# DCP23.net
KiCad netlist of a schematic drawn in EAGLE
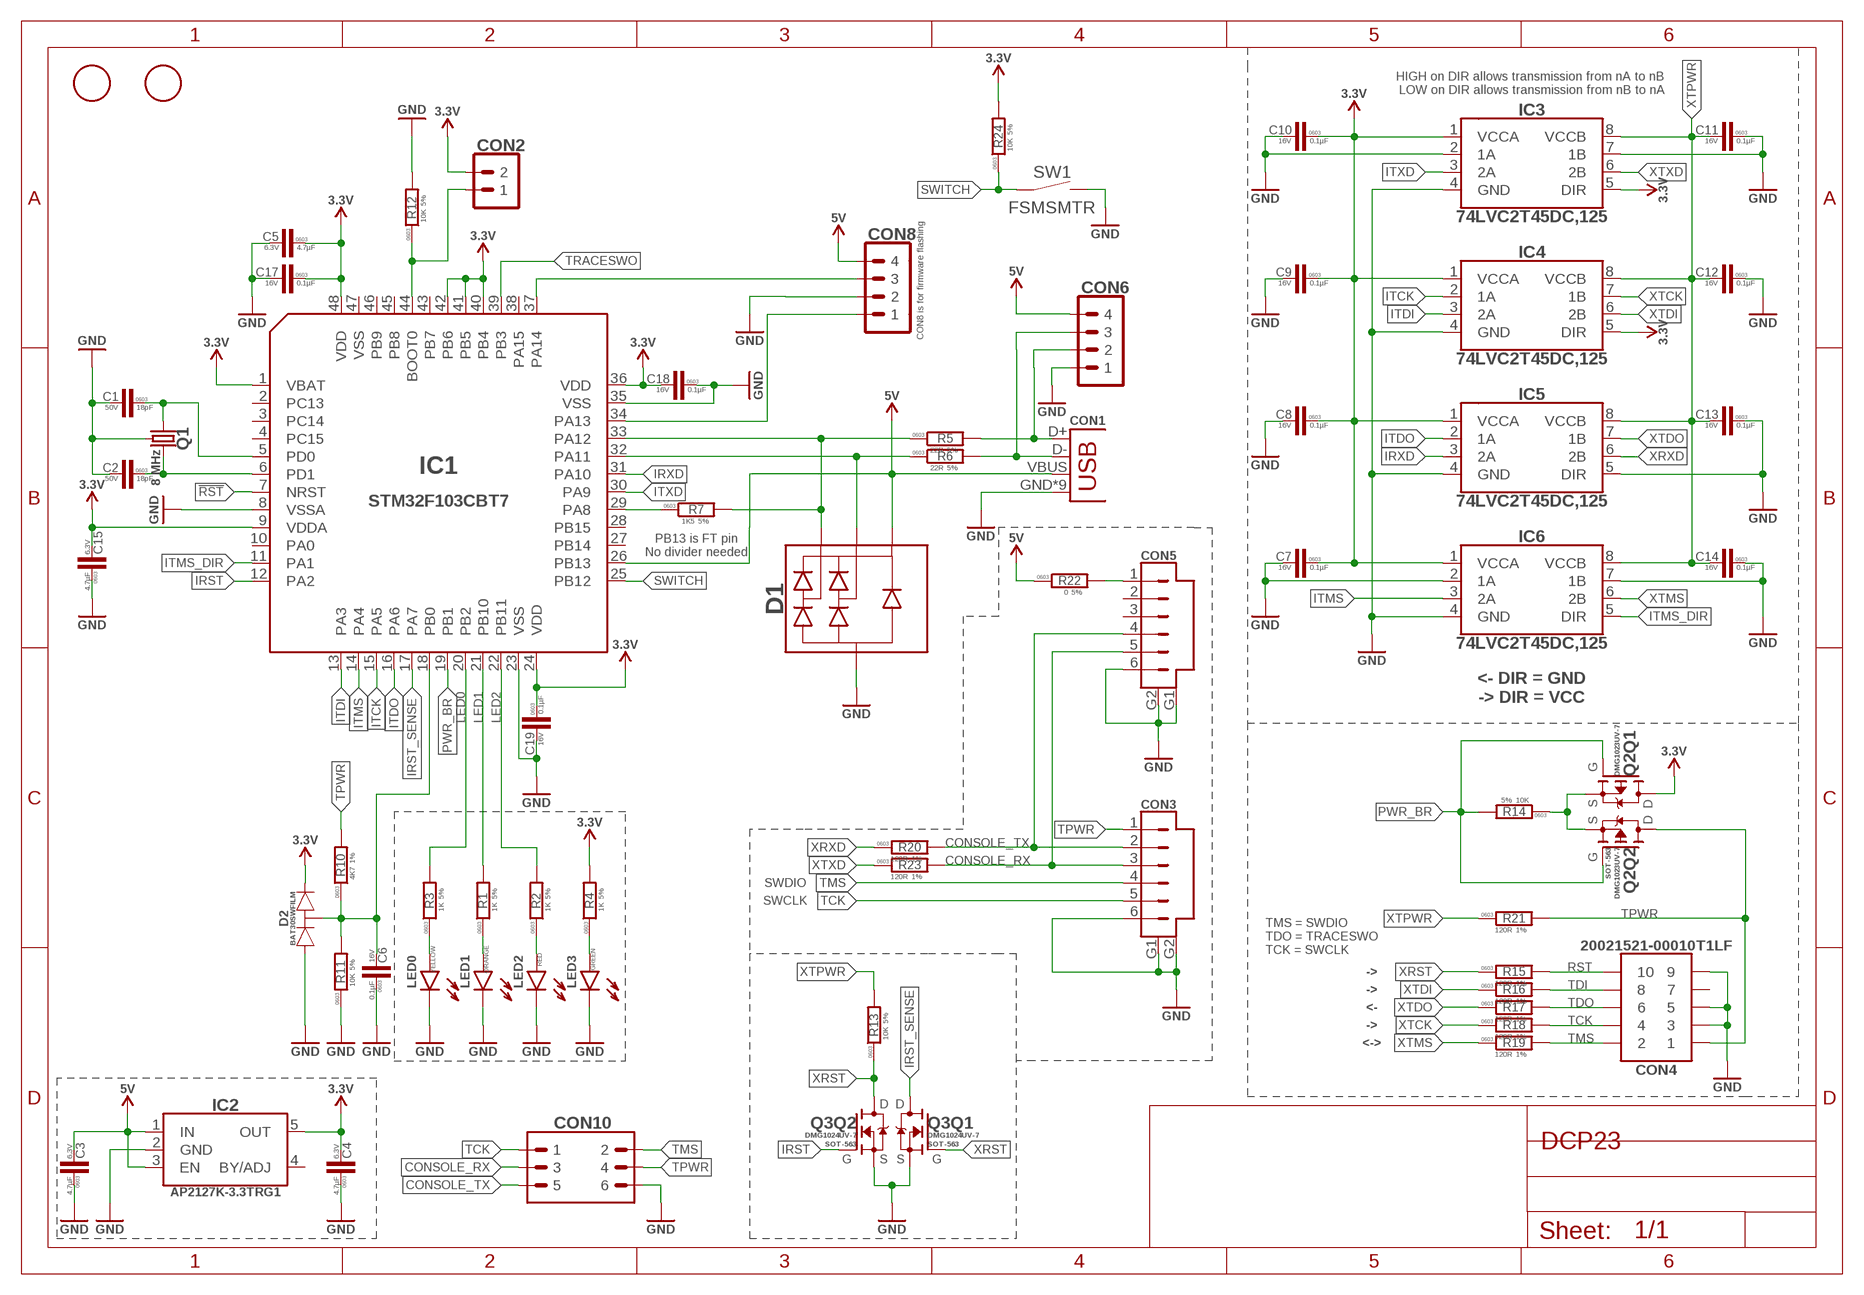
[diagram p0: schematic, sheet 1]

(export (version "E")
  (design (tool "Eeschema 10.0.6"))
  (components
    (comp (ref "C1")
      (value "18pF")
      (footprint "eagle-import:C0603")
      (fields
        (field (name "MANF") "TDK Corporation")
        (field (name "PACKAGE") "0603")
        (field (name "TOLERANCE") "+-5%")
        (field (name "VOLTAGE") "50V")
      )
      (libsource (lib "eagle-import") (part "18PF-0603-50V_5%_NP0"))
    )
    (comp (ref "C2")
      (value "18pF")
      (footprint "eagle-import:C0603")
      (fields
        (field (name "MANF") "TDK Corporation")
        (field (name "PACKAGE") "0603")
        (field (name "TOLERANCE") "+-5%")
        (field (name "VOLTAGE") "50V")
      )
      (libsource (lib "eagle-import") (part "18PF-0603-50V_5%_NP0"))
    )
    (comp (ref "C3")
      (value "4.7µF")
      (footprint "eagle-import:C0603")
      (fields
        (field (name "MANF") "Murata Electronics North America")
        (field (name "PACKAGE") "0603")
        (field (name "TOLERANCE") "+-10%")
        (field (name "VOLTAGE") "6.3V")
      )
      (libsource (lib "eagle-import") (part "4.7µF-0603-6.3V_10%_X5R"))
    )
    (comp (ref "C4")
      (value "4.7µF")
      (footprint "eagle-import:C0603")
      (fields
        (field (name "MANF") "Murata Electronics North America")
        (field (name "PACKAGE") "0603")
        (field (name "TOLERANCE") "+-10%")
        (field (name "VOLTAGE") "6.3V")
      )
      (libsource (lib "eagle-import") (part "4.7µF-0603-6.3V_10%_X5R"))
    )
    (comp (ref "C5")
      (value "4.7µF")
      (footprint "eagle-import:C0603")
      (fields
        (field (name "MANF") "Murata Electronics North America")
        (field (name "PACKAGE") "0603")
        (field (name "TOLERANCE") "+-10%")
        (field (name "VOLTAGE") "6.3V")
      )
      (libsource (lib "eagle-import") (part "4.7µF-0603-6.3V_10%_X5R"))
    )
    (comp (ref "C6")
      (value "0.1µF")
      (footprint "eagle-import:C0603")
      (fields
        (field (name "MANF") "Murata Electronics North America")
        (field (name "PACKAGE") "0603")
        (field (name "TOLERANCE") "+-10%")
        (field (name "VOLTAGE") "16V")
      )
      (libsource (lib "eagle-import") (part "0.1µF-0603-16V_10%_X7R"))
    )
    (comp (ref "C7")
      (value "0.1µF")
      (footprint "eagle-import:C0603")
      (fields
        (field (name "MANF") "Murata Electronics North America")
        (field (name "PACKAGE") "0603")
        (field (name "TOLERANCE") "+-10%")
        (field (name "VOLTAGE") "16V")
      )
      (libsource (lib "eagle-import") (part "0.1µF-0603-16V_10%_X7R"))
    )
    (comp (ref "C8")
      (value "0.1µF")
      (footprint "eagle-import:C0603")
      (fields
        (field (name "MANF") "Murata Electronics North America")
        (field (name "PACKAGE") "0603")
        (field (name "TOLERANCE") "+-10%")
        (field (name "VOLTAGE") "16V")
      )
      (libsource (lib "eagle-import") (part "0.1µF-0603-16V_10%_X7R"))
    )
    (comp (ref "C9")
      (value "0.1µF")
      (footprint "eagle-import:C0603")
      (fields
        (field (name "MANF") "Murata Electronics North America")
        (field (name "PACKAGE") "0603")
        (field (name "TOLERANCE") "+-10%")
        (field (name "VOLTAGE") "16V")
      )
      (libsource (lib "eagle-import") (part "0.1µF-0603-16V_10%_X7R"))
    )
    (comp (ref "C10")
      (value "0.1µF")
      (footprint "eagle-import:C0603")
      (fields
        (field (name "MANF") "Murata Electronics North America")
        (field (name "PACKAGE") "0603")
        (field (name "TOLERANCE") "+-10%")
        (field (name "VOLTAGE") "16V")
      )
      (libsource (lib "eagle-import") (part "0.1µF-0603-16V_10%_X7R"))
    )
    (comp (ref "C11")
      (value "0.1µF")
      (footprint "eagle-import:C0603")
      (fields
        (field (name "MANF") "Murata Electronics North America")
        (field (name "PACKAGE") "0603")
        (field (name "TOLERANCE") "+-10%")
        (field (name "VOLTAGE") "16V")
      )
      (libsource (lib "eagle-import") (part "0.1µF-0603-16V_10%_X7R"))
    )
    (comp (ref "C12")
      (value "0.1µF")
      (footprint "eagle-import:C0603")
      (fields
        (field (name "MANF") "Murata Electronics North America")
        (field (name "PACKAGE") "0603")
        (field (name "TOLERANCE") "+-10%")
        (field (name "VOLTAGE") "16V")
      )
      (libsource (lib "eagle-import") (part "0.1µF-0603-16V_10%_X7R"))
    )
    (comp (ref "C13")
      (value "0.1µF")
      (footprint "eagle-import:C0603")
      (fields
        (field (name "MANF") "Murata Electronics North America")
        (field (name "PACKAGE") "0603")
        (field (name "TOLERANCE") "+-10%")
        (field (name "VOLTAGE") "16V")
      )
      (libsource (lib "eagle-import") (part "0.1µF-0603-16V_10%_X7R"))
    )
    (comp (ref "C14")
      (value "0.1µF")
      (footprint "eagle-import:C0603")
      (fields
        (field (name "MANF") "Murata Electronics North America")
        (field (name "PACKAGE") "0603")
        (field (name "TOLERANCE") "+-10%")
        (field (name "VOLTAGE") "16V")
      )
      (libsource (lib "eagle-import") (part "0.1µF-0603-16V_10%_X7R"))
    )
    (comp (ref "C15")
      (value "4.7µF")
      (footprint "eagle-import:C0603")
      (fields
        (field (name "MANF") "Murata Electronics North America")
        (field (name "PACKAGE") "0603")
        (field (name "TOLERANCE") "+-10%")
        (field (name "VOLTAGE") "6.3V")
      )
      (libsource (lib "eagle-import") (part "4.7µF-0603-6.3V_10%_X5R"))
    )
    (comp (ref "C17")
      (value "0.1µF")
      (footprint "eagle-import:C0603")
      (fields
        (field (name "MANF") "Murata Electronics North America")
        (field (name "PACKAGE") "0603")
        (field (name "TOLERANCE") "+-10%")
        (field (name "VOLTAGE") "16V")
      )
      (libsource (lib "eagle-import") (part "0.1µF-0603-16V_10%_X7R"))
    )
    (comp (ref "C18")
      (value "0.1µF")
      (footprint "eagle-import:C0603")
      (fields
        (field (name "MANF") "Murata Electronics North America")
        (field (name "PACKAGE") "0603")
        (field (name "TOLERANCE") "+-10%")
        (field (name "VOLTAGE") "16V")
      )
      (libsource (lib "eagle-import") (part "0.1µF-0603-16V_10%_X7R"))
    )
    (comp (ref "C19")
      (value "0.1µF")
      (footprint "eagle-import:C0603")
      (fields
        (field (name "MANF") "Murata Electronics North America")
        (field (name "PACKAGE") "0603")
        (field (name "TOLERANCE") "+-10%")
        (field (name "VOLTAGE") "16V")
      )
      (libsource (lib "eagle-import") (part "0.1µF-0603-16V_10%_X7R"))
    )
    (comp (ref "CON1")
      (value "USB-1")
      (footprint "eagle-import:MICRO_USB_WITH_PEGS")
      (fields (field (name "MANF") "FCI"))
      (libsource (lib "eagle-import") (part "USB-1"))
    )
    (comp (ref "CON2")
      (value "PINHEAD_1X02-2")
      (footprint "eagle-import:1X02-PTH-2")
      (libsource (lib "eagle-import") (part "PINHEAD_1X02-2"))
    )
    (comp (ref "CON3")
      (value "CON-6P-SM06B")
      (footprint "eagle-import:SM06B")
      (fields (field (name "MANF") "JST Sales America Inc"))
      (libsource (lib "eagle-import") (part "CON-6P-SM06B"))
    )
    (comp (ref "CON4")
      (value "CON-2X5P")
      (footprint "eagle-import:200215-00010T1LF")
      (fields (field (name "MANF#") "20021521-00010T1LF") (field (name "MANF") "Amphenol ICC (FCI)"))
      (libsource (lib "eagle-import") (part "CON-2X5P"))
    )
    (comp (ref "CON5")
      (value "CON-6P-DF13")
      (footprint "eagle-import:DF13C-6P-1.25V")
      (fields (field (name "MANF") "Hirose Electric Co Ltd"))
      (libsource (lib "eagle-import") (part "CON-6P-DF13"))
    )
    (comp (ref "CON6")
      (value "PINHEAD_1X04-2.54")
      (footprint "eagle-import:1X04-PTH-2.54")
      (libsource (lib "eagle-import") (part "PINHEAD_1X04-2.54"))
    )
    (comp (ref "CON8")
      (value "PINHEAD_1X04-2.54")
      (footprint "eagle-import:1X04-PTH-2.54")
      (libsource (lib "eagle-import") (part "PINHEAD_1X04-2.54"))
    )
    (comp (ref "CON10")
      (value "PINHEAD_2X03-PTH-2.54")
      (footprint "eagle-import:2X03-PTH-2.54")
      (libsource (lib "eagle-import") (part "PINHEAD_2X03-PTH-2.54"))
    )
    (comp (ref "D1")
      (value "PRTR5V0U2X")
      (footprint "eagle-import:SOT143B")
      (fields (field (name "MANF") "NXP USA Inc"))
      (libsource (lib "eagle-import") (part "PRTR5V0U2X"))
    )
    (comp (ref "D2")
      (value "BAT30SWFILM")
      (footprint "eagle-import:SC70")
      (fields (field (name "MANF#") "BAT30SWFILM") (field (name "MANF") "STMicroelectronics"))
      (libsource (lib "eagle-import") (part "BAT30SWFILM"))
    )
    (comp (ref "IC1")
      (value "STM32F103CBT7")
      (footprint "eagle-import:LQFP48")
      (fields (field (name "MANF#") "STM32F103CBT7") (field (name "MANF") "STMicroelectronics"))
      (libsource (lib "eagle-import") (part "STM32F103CBT7"))
    )
    (comp (ref "IC2")
      (value "AP2127-3.3")
      (footprint "eagle-import:SOT23-5")
      (fields (field (name "MANF") "Diodes Incorporated") (field (name "MANF#") "AP2127K-3.3TRG1"))
      (libsource (lib "eagle-import") (part "AP2127-3.3"))
    )
    (comp (ref "IC3")
      (value "74LVC2T45")
      (footprint "eagle-import:VSSOP8")
      (fields (field (name "MANF#") "74LVC2T45DC,125") (field (name "MANF") "Nexperia USA Inc"))
      (libsource (lib "eagle-import") (part "74LVC2T45"))
    )
    (comp (ref "IC4")
      (value "74LVC2T45")
      (footprint "eagle-import:VSSOP8")
      (fields (field (name "MANF#") "74LVC2T45DC,125") (field (name "MANF") "Nexperia USA Inc"))
      (libsource (lib "eagle-import") (part "74LVC2T45"))
    )
    (comp (ref "IC5")
      (value "74LVC2T45")
      (footprint "eagle-import:VSSOP8")
      (fields (field (name "MANF#") "74LVC2T45DC,125") (field (name "MANF") "Nexperia USA Inc"))
      (libsource (lib "eagle-import") (part "74LVC2T45"))
    )
    (comp (ref "IC6")
      (value "74LVC2T45")
      (footprint "eagle-import:VSSOP8")
      (fields (field (name "MANF#") "74LVC2T45DC,125") (field (name "MANF") "Nexperia USA Inc"))
      (libsource (lib "eagle-import") (part "74LVC2T45"))
    )
    (comp (ref "LED0")
      (value "LED-0603")
      (footprint "eagle-import:LED0603")
      (fields (field (name "COLOR") "YELLOW"))
      (libsource (lib "eagle-import") (part "LED-0603"))
    )
    (comp (ref "LED1")
      (value "LED-0603")
      (footprint "eagle-import:LED0603")
      (fields (field (name "COLOR") "ORANGE"))
      (libsource (lib "eagle-import") (part "LED-0603"))
    )
    (comp (ref "LED2")
      (value "LED-0603")
      (footprint "eagle-import:LED0603")
      (fields (field (name "COLOR") "RED"))
      (libsource (lib "eagle-import") (part "LED-0603"))
    )
    (comp (ref "LED3")
      (value "LED-0603")
      (footprint "eagle-import:LED0603")
      (fields (field (name "COLOR") "GREEN"))
      (libsource (lib "eagle-import") (part "LED-0603"))
    )
    (comp (ref "Q1")
      (value "8 MHz")
      (footprint "eagle-import:OSCILLATOR-5.0X3.2-4P")
      (fields (field (name "MANF") "Abracon LLC"))
      (libsource (lib "eagle-import") (part "CRYSTAL-4P-3.2X5-4P-8MHZ"))
    )
    (comp (ref "Q2")
      (value "DMG1023UV-7")
      (footprint "eagle-import:SOT-563")
      (fields
        (field (name "MANF#") "DMG1023UV-7")
        (field (name "MANF") "Diodes Incorporated")
        (field (name "PACKAGE") "SOT-563")
      )
      (libsource (lib "eagle-import") (part "DMG1023UV-7"))
    )
    (comp (ref "Q3")
      (value "DMG1024UV-7")
      (footprint "eagle-import:SOT-563")
      (fields
        (field (name "MANF#") "DMG1024UV-7")
        (field (name "PACKAGE") "SOT-563")
        (field (name "MANF") "Diodes Incorporated")
      )
      (libsource (lib "eagle-import") (part "DMG1024UV-7"))
    )
    (comp (ref "R1")
      (value "1K")
      (footprint "eagle-import:R0603")
      (fields (field (name "MANF") "Yageo") (field (name "PACKAGE") "0603") (field (name "TOLERANCE") "5%"))
      (libsource (lib "eagle-import") (part "1K-0603-5%"))
    )
    (comp (ref "R2")
      (value "1K")
      (footprint "eagle-import:R0603")
      (fields (field (name "MANF") "Yageo") (field (name "PACKAGE") "0603") (field (name "TOLERANCE") "5%"))
      (libsource (lib "eagle-import") (part "1K-0603-5%"))
    )
    (comp (ref "R3")
      (value "1K")
      (footprint "eagle-import:R0603")
      (fields (field (name "MANF") "Yageo") (field (name "PACKAGE") "0603") (field (name "TOLERANCE") "5%"))
      (libsource (lib "eagle-import") (part "1K-0603-5%"))
    )
    (comp (ref "R4")
      (value "1K")
      (footprint "eagle-import:R0603")
      (fields (field (name "MANF") "Yageo") (field (name "PACKAGE") "0603") (field (name "TOLERANCE") "5%"))
      (libsource (lib "eagle-import") (part "1K-0603-5%"))
    )
    (comp (ref "R5")
      (value "22R")
      (footprint "eagle-import:R0603")
      (fields (field (name "PACKAGE") "0603") (field (name "TOLERANCE") "5%") (field (name "MANF") "Yageo"))
      (libsource (lib "eagle-import") (part "R-0603-5%"))
    )
    (comp (ref "R6")
      (value "22R")
      (footprint "eagle-import:R0603")
      (fields (field (name "PACKAGE") "0603") (field (name "TOLERANCE") "5%") (field (name "MANF") "Yageo"))
      (libsource (lib "eagle-import") (part "R-0603-5%"))
    )
    (comp (ref "R7")
      (value "1K5")
      (footprint "eagle-import:R0603")
      (fields (field (name "PACKAGE") "0603") (field (name "TOLERANCE") "5%") (field (name "MANF") "Yageo"))
      (libsource (lib "eagle-import") (part "R-0603-5%"))
    )
    (comp (ref "R10")
      (value "4K7")
      (footprint "eagle-import:R0603")
      (fields (field (name "MANF") "Yageo") (field (name "PACKAGE") "0603") (field (name "TOLERANCE") "1%"))
      (libsource (lib "eagle-import") (part "4K7-0603-1%"))
    )
    (comp (ref "R11")
      (value "10K")
      (footprint "eagle-import:R0603")
      (fields (field (name "MANF") "Yageo") (field (name "PACKAGE") "0603") (field (name "TOLERANCE") "5%"))
      (libsource (lib "eagle-import") (part "10K-0603-5%"))
    )
    (comp (ref "R12")
      (value "10K")
      (footprint "eagle-import:R0603")
      (fields (field (name "MANF") "Yageo") (field (name "PACKAGE") "0603") (field (name "TOLERANCE") "5%"))
      (libsource (lib "eagle-import") (part "10K-0603-5%"))
    )
    (comp (ref "R13")
      (value "10K")
      (footprint "eagle-import:R0603")
      (fields (field (name "MANF") "Yageo") (field (name "PACKAGE") "0603") (field (name "TOLERANCE") "5%"))
      (libsource (lib "eagle-import") (part "10K-0603-5%"))
    )
    (comp (ref "R14")
      (value "10K")
      (footprint "eagle-import:R0603")
      (fields (field (name "MANF") "Yageo") (field (name "PACKAGE") "0603") (field (name "TOLERANCE") "5%"))
      (libsource (lib "eagle-import") (part "10K-0603-5%"))
    )
    (comp (ref "R15")
      (value "120R")
      (footprint "eagle-import:R0603")
      (fields (field (name "MANF") "Yageo") (field (name "PACKAGE") "0603") (field (name "TOLERANCE") "1%"))
      (libsource (lib "eagle-import") (part "120R-0603-1%"))
    )
    (comp (ref "R16")
      (value "120R")
      (footprint "eagle-import:R0603")
      (fields (field (name "MANF") "Yageo") (field (name "PACKAGE") "0603") (field (name "TOLERANCE") "1%"))
      (libsource (lib "eagle-import") (part "120R-0603-1%"))
    )
    (comp (ref "R17")
      (value "120R")
      (footprint "eagle-import:R0603")
      (fields (field (name "MANF") "Yageo") (field (name "PACKAGE") "0603") (field (name "TOLERANCE") "1%"))
      (libsource (lib "eagle-import") (part "120R-0603-1%"))
    )
    (comp (ref "R18")
      (value "120R")
      (footprint "eagle-import:R0603")
      (fields (field (name "MANF") "Yageo") (field (name "PACKAGE") "0603") (field (name "TOLERANCE") "1%"))
      (libsource (lib "eagle-import") (part "120R-0603-1%"))
    )
    (comp (ref "R19")
      (value "120R")
      (footprint "eagle-import:R0603")
      (fields (field (name "MANF") "Yageo") (field (name "PACKAGE") "0603") (field (name "TOLERANCE") "1%"))
      (libsource (lib "eagle-import") (part "120R-0603-1%"))
    )
    (comp (ref "R20")
      (value "120R")
      (footprint "eagle-import:R0603")
      (fields (field (name "MANF") "Yageo") (field (name "PACKAGE") "0603") (field (name "TOLERANCE") "1%"))
      (libsource (lib "eagle-import") (part "120R-0603-1%"))
    )
    (comp (ref "R21")
      (value "120R")
      (footprint "eagle-import:R0603")
      (fields (field (name "MANF") "Yageo") (field (name "PACKAGE") "0603") (field (name "TOLERANCE") "1%"))
      (libsource (lib "eagle-import") (part "120R-0603-1%"))
    )
    (comp (ref "R22")
      (value "0")
      (footprint "eagle-import:R0603")
      (fields (field (name "MANF") "Yageo") (field (name "PACKAGE") "0603") (field (name "TOLERANCE") "5%"))
      (libsource (lib "eagle-import") (part "0R-0603-5%"))
    )
    (comp (ref "R23")
      (value "120R")
      (footprint "eagle-import:R0603")
      (fields (field (name "MANF") "Yageo") (field (name "PACKAGE") "0603") (field (name "TOLERANCE") "1%"))
      (libsource (lib "eagle-import") (part "120R-0603-1%"))
    )
    (comp (ref "R24")
      (value "10K")
      (footprint "eagle-import:R0603")
      (fields (field (name "MANF") "Yageo") (field (name "PACKAGE") "0603") (field (name "TOLERANCE") "5%"))
      (libsource (lib "eagle-import") (part "10K-0603-5%"))
    )
    (comp (ref "SW1")
      (value "TACT_SWITCH-FSMSM")
      (footprint "eagle-import:FSMSM")
      (fields (field (name "MANF") "TE Connectivity ALCOSWITCH Switches"))
      (libsource (lib "eagle-import") (part "TACT_SWITCH-FSMSM"))
    )
    (comp (ref "U$9")
      (value "FIDUCIALMOUNT")
      (footprint "eagle-import:FIDUCIA-MOUNT")
      (libsource (lib "eagle-import") (part "FIDUCIALMOUNT"))
    )
    (comp (ref "U$10")
      (value "FIDUCIALMOUNT")
      (footprint "eagle-import:FIDUCIA-MOUNT")
      (libsource (lib "eagle-import") (part "FIDUCIALMOUNT"))
    )
  )
  (nets
    (net (code "1") (name "/LED0") (class "Default")
      (node (ref "IC1") (pin "20") (pinfunction "PB2_20") (pintype "bidirectional"))
      (node (ref "R3") (pin "P$2") (pinfunction "2_P$2") (pintype "passive"))
    )
    (net (code "2") (name "/LED1") (class "Default")
      (node (ref "IC1") (pin "21") (pinfunction "PB10_21") (pintype "bidirectional"))
      (node (ref "R1") (pin "P$2") (pinfunction "2_P$2") (pintype "passive"))
    )
    (net (code "3") (name "/LED2") (class "Default")
      (node (ref "IC1") (pin "22") (pinfunction "PB11_22") (pintype "bidirectional"))
      (node (ref "R2") (pin "P$2") (pinfunction "2_P$2") (pintype "passive"))
    )
    (net (code "4") (name "/RST") (class "Default")
      (node (ref "CON4") (pin "10") (pinfunction "10_10") (pintype "bidirectional"))
      (node (ref "R15") (pin "P$2") (pinfunction "2_P$2") (pintype "passive"))
    )
    (net (code "5") (name "/TDI") (class "Default")
      (node (ref "CON4") (pin "8") (pinfunction "8_8") (pintype "bidirectional"))
      (node (ref "R16") (pin "P$2") (pinfunction "2_P$2") (pintype "passive"))
    )
    (net (code "6") (name "/TDO") (class "Default")
      (node (ref "CON4") (pin "6") (pinfunction "6_6") (pintype "bidirectional"))
      (node (ref "R17") (pin "P$2") (pinfunction "2_P$2") (pintype "passive"))
    )
    (net (code "7") (name "/~{RST}") (class "Default")
      (node (ref "IC1") (pin "7") (pinfunction "NRST_7") (pintype "bidirectional"))
    )
    (net (code "8") (name "3.3V") (class "Default")
      (node (ref "C10") (pin "P$1") (pinfunction "1_P$1") (pintype "passive"))
      (node (ref "C15") (pin "P$2") (pinfunction "2_P$2") (pintype "passive"))
      (node (ref "C17") (pin "P$1") (pinfunction "1_P$1") (pintype "passive"))
      (node (ref "C18") (pin "P$2") (pinfunction "2_P$2") (pintype "passive"))
      (node (ref "C19") (pin "P$1") (pinfunction "1_P$1") (pintype "passive"))
      (node (ref "C4") (pin "P$2") (pinfunction "2_P$2") (pintype "passive"))
      (node (ref "C5") (pin "P$1") (pinfunction "1_P$1") (pintype "passive"))
      (node (ref "C7") (pin "P$1") (pinfunction "1_P$1") (pintype "passive"))
      (node (ref "C8") (pin "P$1") (pinfunction "1_P$1") (pintype "passive"))
      (node (ref "C9") (pin "P$1") (pinfunction "1_P$1") (pintype "passive"))
      (node (ref "CON2") (pin "2") (pinfunction "2_2") (pintype "passive"))
      (node (ref "D2") (pin "2") (pinfunction "C_2") (pintype "passive"))
      (node (ref "IC1") (pin "1") (pinfunction "VBAT_1") (pintype "bidirectional"))
      (node (ref "IC1") (pin "24") (pinfunction "VDD_24") (pintype "bidirectional"))
      (node (ref "IC1") (pin "36") (pinfunction "VDD_36") (pintype "bidirectional"))
      (node (ref "IC1") (pin "40") (pinfunction "PB4_40") (pintype "bidirectional"))
      (node (ref "IC1") (pin "41") (pinfunction "PB5_41") (pintype "bidirectional"))
      (node (ref "IC1") (pin "42") (pinfunction "PB6_42") (pintype "bidirectional"))
      (node (ref "IC1") (pin "48") (pinfunction "VDD_48") (pintype "bidirectional"))
      (node (ref "IC1") (pin "9") (pinfunction "VDDA_9") (pintype "bidirectional"))
      (node (ref "IC2") (pin "5") (pinfunction "OUT_5") (pintype "power_in"))
      (node (ref "IC3") (pin "1") (pinfunction "VCCA_1") (pintype "bidirectional"))
      (node (ref "IC3") (pin "5") (pinfunction "DIR_5") (pintype "bidirectional"))
      (node (ref "IC4") (pin "1") (pinfunction "VCCA_1") (pintype "bidirectional"))
      (node (ref "IC4") (pin "5") (pinfunction "DIR_5") (pintype "bidirectional"))
      (node (ref "IC5") (pin "1") (pinfunction "VCCA_1") (pintype "bidirectional"))
      (node (ref "IC6") (pin "1") (pinfunction "VCCA_1") (pintype "bidirectional"))
      (node (ref "Q2") (pin "3") (pinfunction "D_3") (pintype "passive"))
      (node (ref "R24") (pin "P$2") (pinfunction "2_P$2") (pintype "passive"))
      (node (ref "R4") (pin "P$2") (pinfunction "2_P$2") (pintype "passive"))
    )
    (net (code "9") (name "5V") (class "Default")
      (node (ref "C3") (pin "P$2") (pinfunction "2_P$2") (pintype "passive"))
      (node (ref "CON1") (pin "VBUS") (pinfunction "VBUS_VBUS") (pintype "bidirectional"))
      (node (ref "CON6") (pin "4") (pinfunction "4_4") (pintype "passive"))
      (node (ref "CON8") (pin "4") (pinfunction "4_4") (pintype "passive"))
      (node (ref "D1") (pin "4") (pinfunction "A_4") (pintype "bidirectional"))
      (node (ref "IC1") (pin "26") (pinfunction "PB13_26") (pintype "bidirectional"))
      (node (ref "IC2") (pin "1") (pinfunction "IN_1") (pintype "power_in"))
      (node (ref "IC2") (pin "3") (pinfunction "EN_3") (pintype "input"))
      (node (ref "R22") (pin "P$1") (pinfunction "1_P$1") (pintype "passive"))
    )
    (net (code "10") (name "CONSOLE_RX") (class "Default")
      (node (ref "CON10") (pin "3") (pinfunction "3_3") (pintype "passive"))
      (node (ref "CON3") (pin "3") (pinfunction "3_3") (pintype "passive"))
      (node (ref "CON5") (pin "5") (pinfunction "5_5") (pintype "passive"))
      (node (ref "R23") (pin "P$2") (pinfunction "2_P$2") (pintype "passive"))
    )
    (net (code "11") (name "CONSOLE_TX") (class "Default")
      (node (ref "CON10") (pin "5") (pinfunction "5_5") (pintype "passive"))
      (node (ref "CON3") (pin "2") (pinfunction "2_2") (pintype "passive"))
      (node (ref "CON5") (pin "4") (pinfunction "4_4") (pintype "passive"))
      (node (ref "R20") (pin "P$2") (pinfunction "2_P$2") (pintype "passive"))
    )
    (net (code "12") (name "GND") (class "Default")
      (node (ref "C1") (pin "P$2") (pinfunction "2_P$2") (pintype "passive"))
      (node (ref "C10") (pin "P$2") (pinfunction "2_P$2") (pintype "passive"))
      (node (ref "C11") (pin "P$1") (pinfunction "1_P$1") (pintype "passive"))
      (node (ref "C12") (pin "P$1") (pinfunction "1_P$1") (pintype "passive"))
      (node (ref "C13") (pin "P$1") (pinfunction "1_P$1") (pintype "passive"))
      (node (ref "C14") (pin "P$1") (pinfunction "1_P$1") (pintype "passive"))
      (node (ref "C15") (pin "P$1") (pinfunction "1_P$1") (pintype "passive"))
      (node (ref "C17") (pin "P$2") (pinfunction "2_P$2") (pintype "passive"))
      (node (ref "C18") (pin "P$1") (pinfunction "1_P$1") (pintype "passive"))
      (node (ref "C19") (pin "P$2") (pinfunction "2_P$2") (pintype "passive"))
      (node (ref "C2") (pin "P$2") (pinfunction "2_P$2") (pintype "passive"))
      (node (ref "C3") (pin "P$1") (pinfunction "1_P$1") (pintype "passive"))
      (node (ref "C4") (pin "P$1") (pinfunction "1_P$1") (pintype "passive"))
      (node (ref "C5") (pin "P$2") (pinfunction "2_P$2") (pintype "passive"))
      (node (ref "C6") (pin "P$1") (pinfunction "1_P$1") (pintype "passive"))
      (node (ref "C7") (pin "P$2") (pinfunction "2_P$2") (pintype "passive"))
      (node (ref "C8") (pin "P$2") (pinfunction "2_P$2") (pintype "passive"))
      (node (ref "C9") (pin "P$2") (pinfunction "2_P$2") (pintype "passive"))
      (node (ref "CON1") (pin "GND") (pinfunction "GND_GND") (pintype "bidirectional"))
      (node (ref "CON1") (pin "GND1") (pinfunction "GND_GND1") (pintype "bidirectional"))
      (node (ref "CON1") (pin "GND2") (pinfunction "GND_GND2") (pintype "bidirectional"))
      (node (ref "CON1") (pin "GND3") (pinfunction "GND_GND3") (pintype "bidirectional"))
      (node (ref "CON1") (pin "GND4") (pinfunction "GND_GND4") (pintype "bidirectional"))
      (node (ref "CON1") (pin "P$1") (pinfunction "GND_P$1") (pintype "bidirectional"))
      (node (ref "CON1") (pin "P$2") (pinfunction "GND_P$2") (pintype "bidirectional"))
      (node (ref "CON1") (pin "P$3") (pinfunction "GND_P$3") (pintype "bidirectional"))
      (node (ref "CON1") (pin "P$4") (pinfunction "GND_P$4") (pintype "bidirectional"))
      (node (ref "CON10") (pin "6") (pinfunction "6_6") (pintype "passive"))
      (node (ref "CON3") (pin "6") (pinfunction "6_6") (pintype "passive"))
      (node (ref "CON3") (pin "G1") (pinfunction "G1_G1") (pintype "passive"))
      (node (ref "CON3") (pin "G2") (pinfunction "G2_G2") (pintype "passive"))
      (node (ref "CON4") (pin "3") (pinfunction "3_3") (pintype "bidirectional"))
      (node (ref "CON4") (pin "5") (pinfunction "5_5") (pintype "bidirectional"))
      (node (ref "CON4") (pin "9") (pinfunction "9_9") (pintype "bidirectional"))
      (node (ref "CON5") (pin "6") (pinfunction "6_6") (pintype "passive"))
      (node (ref "CON5") (pin "G1") (pinfunction "G2_G1") (pintype "passive"))
      (node (ref "CON5") (pin "G2") (pinfunction "G1_G2") (pintype "passive"))
      (node (ref "CON6") (pin "1") (pinfunction "1_1") (pintype "passive"))
      (node (ref "CON8") (pin "2") (pinfunction "2_2") (pintype "passive"))
      (node (ref "D1") (pin "1") (pinfunction "C_1") (pintype "bidirectional"))
      (node (ref "D2") (pin "1") (pinfunction "A_1") (pintype "passive"))
      (node (ref "IC1") (pin "23") (pinfunction "VSS_23") (pintype "bidirectional"))
      (node (ref "IC1") (pin "35") (pinfunction "VSS_35") (pintype "bidirectional"))
      (node (ref "IC1") (pin "8") (pinfunction "VSSA_8") (pintype "bidirectional"))
      (node (ref "IC2") (pin "2") (pinfunction "GND_2") (pintype "power_in"))
      (node (ref "IC3") (pin "2") (pinfunction "1A_2") (pintype "bidirectional"))
      (node (ref "IC3") (pin "4") (pinfunction "GND_4") (pintype "bidirectional"))
      (node (ref "IC3") (pin "7") (pinfunction "1B_7") (pintype "bidirectional"))
      (node (ref "IC4") (pin "4") (pinfunction "GND_4") (pintype "bidirectional"))
      (node (ref "IC5") (pin "4") (pinfunction "GND_4") (pintype "bidirectional"))
      (node (ref "IC5") (pin "5") (pinfunction "DIR_5") (pintype "bidirectional"))
      (node (ref "IC6") (pin "2") (pinfunction "1A_2") (pintype "bidirectional"))
      (node (ref "IC6") (pin "4") (pinfunction "GND_4") (pintype "bidirectional"))
      (node (ref "IC6") (pin "7") (pinfunction "1B_7") (pintype "bidirectional"))
      (node (ref "LED0") (pin "C") (pinfunction "C_C") (pintype "bidirectional"))
      (node (ref "LED1") (pin "C") (pinfunction "C_C") (pintype "bidirectional"))
      (node (ref "LED2") (pin "C") (pinfunction "C_C") (pintype "bidirectional"))
      (node (ref "LED3") (pin "C") (pinfunction "C_C") (pintype "bidirectional"))
      (node (ref "Q1") (pin "2") (pinfunction "GND_2") (pintype "bidirectional"))
      (node (ref "Q1") (pin "4") (pinfunction "GND_4") (pintype "bidirectional"))
      (node (ref "Q3") (pin "1") (pinfunction "S_1") (pintype "passive"))
      (node (ref "Q3") (pin "4") (pinfunction "S_4") (pintype "passive"))
      (node (ref "R11") (pin "P$1") (pinfunction "1_P$1") (pintype "passive"))
      (node (ref "R12") (pin "P$2") (pinfunction "2_P$2") (pintype "passive"))
      (node (ref "SW1") (pin "P$2") (pinfunction "2_P$2") (pintype "bidirectional"))
    )
    (net (code "13") (name "IRST") (class "Default")
      (node (ref "IC1") (pin "12") (pinfunction "PA2_12") (pintype "bidirectional"))
      (node (ref "Q3") (pin "5") (pinfunction "G_5") (pintype "passive"))
    )
    (net (code "14") (name "IRST_SENSE") (class "Default")
      (node (ref "IC1") (pin "17") (pinfunction "PA7_17") (pintype "bidirectional"))
      (node (ref "Q3") (pin "6") (pinfunction "D_6") (pintype "passive"))
    )
    (net (code "15") (name "IRXD") (class "Default")
      (node (ref "IC1") (pin "31") (pinfunction "PA10_31") (pintype "bidirectional"))
      (node (ref "IC5") (pin "3") (pinfunction "2A_3") (pintype "bidirectional"))
    )
    (net (code "16") (name "ITCK") (class "Default")
      (node (ref "IC1") (pin "15") (pinfunction "PA5_15") (pintype "bidirectional"))
      (node (ref "IC4") (pin "2") (pinfunction "1A_2") (pintype "bidirectional"))
    )
    (net (code "17") (name "ITDI") (class "Default")
      (node (ref "IC1") (pin "13") (pinfunction "PA3_13") (pintype "bidirectional"))
      (node (ref "IC4") (pin "3") (pinfunction "2A_3") (pintype "bidirectional"))
    )
    (net (code "18") (name "ITDO") (class "Default")
      (node (ref "IC1") (pin "16") (pinfunction "PA6_16") (pintype "bidirectional"))
      (node (ref "IC5") (pin "2") (pinfunction "1A_2") (pintype "bidirectional"))
    )
    (net (code "19") (name "ITMS") (class "Default")
      (node (ref "IC1") (pin "14") (pinfunction "PA4_14") (pintype "bidirectional"))
      (node (ref "IC6") (pin "3") (pinfunction "2A_3") (pintype "bidirectional"))
    )
    (net (code "20") (name "ITMS_DIR") (class "Default")
      (node (ref "IC1") (pin "11") (pinfunction "PA1_11") (pintype "bidirectional"))
      (node (ref "IC6") (pin "5") (pinfunction "DIR_5") (pintype "bidirectional"))
    )
    (net (code "21") (name "ITXD") (class "Default")
      (node (ref "IC1") (pin "30") (pinfunction "PA9_30") (pintype "bidirectional"))
      (node (ref "IC3") (pin "3") (pinfunction "2A_3") (pintype "bidirectional"))
    )
    (net (code "22") (name "Net-(C1-1)") (class "Default")
      (node (ref "C1") (pin "P$1") (pinfunction "1_P$1") (pintype "passive"))
      (node (ref "IC1") (pin "5") (pinfunction "PD0_5") (pintype "bidirectional"))
      (node (ref "Q1") (pin "1") (pinfunction "1_1") (pintype "passive"))
    )
    (net (code "23") (name "Net-(C2-1)") (class "Default")
      (node (ref "C2") (pin "P$1") (pinfunction "1_P$1") (pintype "passive"))
      (node (ref "IC1") (pin "6") (pinfunction "PD1_6") (pintype "bidirectional"))
      (node (ref "Q1") (pin "3") (pinfunction "2_3") (pintype "passive"))
    )
    (net (code "24") (name "Net-(C6-2)") (class "Default")
      (node (ref "C6") (pin "P$2") (pinfunction "2_P$2") (pintype "passive"))
      (node (ref "D2") (pin "3") (pinfunction "COMMON_3") (pintype "bidirectional"))
      (node (ref "IC1") (pin "18") (pinfunction "PB0_18") (pintype "bidirectional"))
      (node (ref "R10") (pin "P$1") (pinfunction "1_P$1") (pintype "passive"))
      (node (ref "R11") (pin "P$2") (pinfunction "2_P$2") (pintype "passive"))
    )
    (net (code "25") (name "Net-(CON1-PadD+)") (class "Default")
      (node (ref "CON1") (pin "D+") (pinfunction "D+_D+") (pintype "bidirectional"))
      (node (ref "CON6") (pin "2") (pinfunction "2_2") (pintype "passive"))
      (node (ref "R5") (pin "2") (pinfunction "2_2") (pintype "passive"))
    )
    (net (code "26") (name "Net-(CON1-PadD-)") (class "Default")
      (node (ref "CON1") (pin "D-") (pinfunction "D-_D-") (pintype "bidirectional"))
      (node (ref "CON6") (pin "3") (pinfunction "3_3") (pintype "passive"))
      (node (ref "R6") (pin "2") (pinfunction "2_2") (pintype "passive"))
    )
    (net (code "27") (name "Net-(D1-D1)") (class "Default")
      (node (ref "D1") (pin "2") (pinfunction "D1_2") (pintype "bidirectional"))
      (node (ref "IC1") (pin "33") (pinfunction "PA12_33") (pintype "bidirectional"))
      (node (ref "R5") (pin "1") (pinfunction "1_1") (pintype "passive"))
      (node (ref "R7") (pin "2") (pinfunction "2_2") (pintype "passive"))
    )
    (net (code "28") (name "Net-(D1-D2)") (class "Default")
      (node (ref "D1") (pin "3") (pinfunction "D2_3") (pintype "bidirectional"))
      (node (ref "IC1") (pin "32") (pinfunction "PA11_32") (pintype "bidirectional"))
      (node (ref "R6") (pin "1") (pinfunction "1_1") (pintype "passive"))
    )
    (net (code "29") (name "Net-(IC1-BOOT0)") (class "Default")
      (node (ref "CON2") (pin "1") (pinfunction "1_1") (pintype "passive"))
      (node (ref "IC1") (pin "44") (pinfunction "BOOT0_44") (pintype "bidirectional"))
      (node (ref "R12") (pin "P$1") (pinfunction "1_P$1") (pintype "passive"))
    )
    (net (code "30") (name "Net-(IC1-PA8)") (class "Default")
      (node (ref "IC1") (pin "29") (pinfunction "PA8_29") (pintype "bidirectional"))
      (node (ref "R7") (pin "1") (pinfunction "1_1") (pintype "passive"))
    )
    (net (code "31") (name "Net-(IC1-PA13)") (class "Default")
      (node (ref "CON8") (pin "1") (pinfunction "1_1") (pintype "passive"))
      (node (ref "IC1") (pin "34") (pinfunction "PA13_34") (pintype "bidirectional"))
    )
    (net (code "32") (name "Net-(IC1-PA14)") (class "Default")
      (node (ref "CON8") (pin "3") (pinfunction "3_3") (pintype "passive"))
      (node (ref "IC1") (pin "37") (pinfunction "PA14_37") (pintype "bidirectional"))
    )
    (net (code "33") (name "Net-(Q2A-S)") (class "Default")
      (node (ref "Q2") (pin "1") (pinfunction "S_1") (pintype "passive"))
      (node (ref "Q2") (pin "4") (pinfunction "S_4") (pintype "passive"))
      (node (ref "R14") (pin "P$1") (pinfunction "1_P$1") (pintype "passive"))
    )
    (net (code "34") (name "Net-(R1-1)") (class "Default")
      (node (ref "LED1") (pin "A") (pinfunction "A_A") (pintype "bidirectional"))
      (node (ref "R1") (pin "P$1") (pinfunction "1_P$1") (pintype "passive"))
    )
    (net (code "35") (name "Net-(R2-1)") (class "Default")
      (node (ref "LED2") (pin "A") (pinfunction "A_A") (pintype "bidirectional"))
      (node (ref "R2") (pin "P$1") (pinfunction "1_P$1") (pintype "passive"))
    )
    (net (code "36") (name "Net-(R3-1)") (class "Default")
      (node (ref "LED0") (pin "A") (pinfunction "A_A") (pintype "bidirectional"))
      (node (ref "R3") (pin "P$1") (pinfunction "1_P$1") (pintype "passive"))
    )
    (net (code "37") (name "Net-(R4-1)") (class "Default")
      (node (ref "LED3") (pin "A") (pinfunction "A_A") (pintype "bidirectional"))
      (node (ref "R4") (pin "P$1") (pinfunction "1_P$1") (pintype "passive"))
    )
    (net (code "38") (name "Net-(R22-2)") (class "Default")
      (node (ref "CON5") (pin "1") (pinfunction "1_1") (pintype "passive"))
      (node (ref "R22") (pin "P$2") (pinfunction "2_P$2") (pintype "passive"))
    )
    (net (code "39") (name "PWR_BR") (class "Default")
      (node (ref "IC1") (pin "19") (pinfunction "PB1_19") (pintype "bidirectional"))
      (node (ref "Q2") (pin "2") (pinfunction "G_2") (pintype "passive"))
      (node (ref "Q2") (pin "5") (pinfunction "G_5") (pintype "passive"))
      (node (ref "R14") (pin "P$2") (pinfunction "2_P$2") (pintype "passive"))
    )
    (net (code "40") (name "SWITCH") (class "Default")
      (node (ref "IC1") (pin "25") (pinfunction "PB12_25") (pintype "bidirectional"))
      (node (ref "R24") (pin "P$1") (pinfunction "1_P$1") (pintype "passive"))
      (node (ref "SW1") (pin "P$1") (pinfunction "1_P$1") (pintype "bidirectional"))
    )
    (net (code "41") (name "TCK") (class "Default")
      (node (ref "CON10") (pin "1") (pinfunction "1_1") (pintype "passive"))
      (node (ref "CON3") (pin "5") (pinfunction "5_5") (pintype "passive"))
      (node (ref "CON4") (pin "4") (pinfunction "4_4") (pintype "bidirectional"))
      (node (ref "R18") (pin "P$2") (pinfunction "2_P$2") (pintype "passive"))
    )
    (net (code "42") (name "TMS") (class "Default")
      (node (ref "CON10") (pin "2") (pinfunction "2_2") (pintype "passive"))
      (node (ref "CON3") (pin "4") (pinfunction "4_4") (pintype "passive"))
      (node (ref "CON4") (pin "2") (pinfunction "2_2") (pintype "bidirectional"))
      (node (ref "R19") (pin "P$2") (pinfunction "2_P$2") (pintype "passive"))
    )
    (net (code "43") (name "TPWR") (class "Default")
      (node (ref "CON10") (pin "4") (pinfunction "4_4") (pintype "passive"))
      (node (ref "CON3") (pin "1") (pinfunction "1_1") (pintype "passive"))
      (node (ref "CON4") (pin "1") (pinfunction "1_1") (pintype "bidirectional"))
      (node (ref "Q2") (pin "6") (pinfunction "D_6") (pintype "passive"))
      (node (ref "R10") (pin "P$2") (pinfunction "2_P$2") (pintype "passive"))
      (node (ref "R21") (pin "P$2") (pinfunction "2_P$2") (pintype "passive"))
    )
    (net (code "44") (name "TRACESWO") (class "Default")
      (node (ref "IC1") (pin "39") (pinfunction "PB3_39") (pintype "bidirectional"))
    )
    (net (code "45") (name "XRST") (class "Default")
      (node (ref "Q3") (pin "2") (pinfunction "G_2") (pintype "passive"))
      (node (ref "Q3") (pin "3") (pinfunction "D_3") (pintype "passive"))
      (node (ref "R13") (pin "P$1") (pinfunction "1_P$1") (pintype "passive"))
      (node (ref "R15") (pin "P$1") (pinfunction "1_P$1") (pintype "passive"))
    )
    (net (code "46") (name "XRXD") (class "Default")
      (node (ref "IC5") (pin "6") (pinfunction "2B_6") (pintype "bidirectional"))
      (node (ref "R20") (pin "P$1") (pinfunction "1_P$1") (pintype "passive"))
    )
    (net (code "47") (name "XTCK") (class "Default")
      (node (ref "IC4") (pin "7") (pinfunction "1B_7") (pintype "bidirectional"))
      (node (ref "R18") (pin "P$1") (pinfunction "1_P$1") (pintype "passive"))
    )
    (net (code "48") (name "XTDI") (class "Default")
      (node (ref "IC4") (pin "6") (pinfunction "2B_6") (pintype "bidirectional"))
      (node (ref "R16") (pin "P$1") (pinfunction "1_P$1") (pintype "passive"))
    )
    (net (code "49") (name "XTDO") (class "Default")
      (node (ref "IC5") (pin "7") (pinfunction "1B_7") (pintype "bidirectional"))
      (node (ref "R17") (pin "P$1") (pinfunction "1_P$1") (pintype "passive"))
    )
    (net (code "50") (name "XTMS") (class "Default")
      (node (ref "IC6") (pin "6") (pinfunction "2B_6") (pintype "bidirectional"))
      (node (ref "R19") (pin "P$1") (pinfunction "1_P$1") (pintype "passive"))
    )
    (net (code "51") (name "XTPWR") (class "Default")
      (node (ref "C11") (pin "P$2") (pinfunction "2_P$2") (pintype "passive"))
      (node (ref "C12") (pin "P$2") (pinfunction "2_P$2") (pintype "passive"))
      (node (ref "C13") (pin "P$2") (pinfunction "2_P$2") (pintype "passive"))
      (node (ref "C14") (pin "P$2") (pinfunction "2_P$2") (pintype "passive"))
      (node (ref "IC3") (pin "8") (pinfunction "VCCB_8") (pintype "bidirectional"))
      (node (ref "IC4") (pin "8") (pinfunction "VCCB_8") (pintype "bidirectional"))
      (node (ref "IC5") (pin "8") (pinfunction "VCCB_8") (pintype "bidirectional"))
      (node (ref "IC6") (pin "8") (pinfunction "VCCB_8") (pintype "bidirectional"))
      (node (ref "R13") (pin "P$2") (pinfunction "2_P$2") (pintype "passive"))
      (node (ref "R21") (pin "P$1") (pinfunction "1_P$1") (pintype "passive"))
    )
    (net (code "52") (name "XTXD") (class "Default")
      (node (ref "IC3") (pin "6") (pinfunction "2B_6") (pintype "bidirectional"))
      (node (ref "R23") (pin "P$1") (pinfunction "1_P$1") (pintype "passive"))
    )
    (net (code "53") (name "unconnected-(CON4-Pad7)") (class "Default")
      (node (ref "CON4") (pin "7") (pinfunction "7_7") (pintype "bidirectional"))
    )
    (net (code "54") (name "unconnected-(CON5-Pad2)") (class "Default")
      (node (ref "CON5") (pin "2") (pinfunction "2_2") (pintype "passive"))
    )
    (net (code "55") (name "unconnected-(CON5-Pad3)") (class "Default")
      (node (ref "CON5") (pin "3") (pinfunction "3_3") (pintype "passive"))
    )
    (net (code "56") (name "unconnected-(IC1-PA0-Pad10)") (class "Default")
      (node (ref "IC1") (pin "10") (pinfunction "PA0_10") (pintype "bidirectional"))
    )
    (net (code "57") (name "unconnected-(IC1-PA15-Pad38)") (class "Default")
      (node (ref "IC1") (pin "38") (pinfunction "PA15_38") (pintype "bidirectional"))
    )
    (net (code "58") (name "unconnected-(IC1-PB7-Pad43)") (class "Default")
      (node (ref "IC1") (pin "43") (pinfunction "PB7_43") (pintype "bidirectional"))
    )
    (net (code "59") (name "unconnected-(IC1-PB8-Pad45)") (class "Default")
      (node (ref "IC1") (pin "45") (pinfunction "PB8_45") (pintype "bidirectional"))
    )
    (net (code "60") (name "unconnected-(IC1-PB9-Pad46)") (class "Default")
      (node (ref "IC1") (pin "46") (pinfunction "PB9_46") (pintype "bidirectional"))
    )
    (net (code "61") (name "unconnected-(IC1-PB14-Pad27)") (class "Default")
      (node (ref "IC1") (pin "27") (pinfunction "PB14_27") (pintype "bidirectional"))
    )
    (net (code "62") (name "unconnected-(IC1-PB15-Pad28)") (class "Default")
      (node (ref "IC1") (pin "28") (pinfunction "PB15_28") (pintype "bidirectional"))
    )
    (net (code "63") (name "unconnected-(IC1-PC13-Pad2)") (class "Default")
      (node (ref "IC1") (pin "2") (pinfunction "PC13_2") (pintype "bidirectional"))
    )
    (net (code "64") (name "unconnected-(IC1-PC14-Pad3)") (class "Default")
      (node (ref "IC1") (pin "3") (pinfunction "PC14_3") (pintype "bidirectional"))
    )
    (net (code "65") (name "unconnected-(IC1-PC15-Pad4)") (class "Default")
      (node (ref "IC1") (pin "4") (pinfunction "PC15_4") (pintype "bidirectional"))
    )
    (net (code "66") (name "unconnected-(IC1-VSS-Pad47)") (class "Default")
      (node (ref "IC1") (pin "47") (pinfunction "VSS_47") (pintype "bidirectional"))
    )
    (net (code "67") (name "unconnected-(IC2-BY{slash}ADJ-Pad4)") (class "Default")
      (node (ref "IC2") (pin "4") (pinfunction "BY/ADJ_4") (pintype "bidirectional"))
    )
  )
)
